# Main.net
KiCad netlist of a schematic drawn in Altium Designer
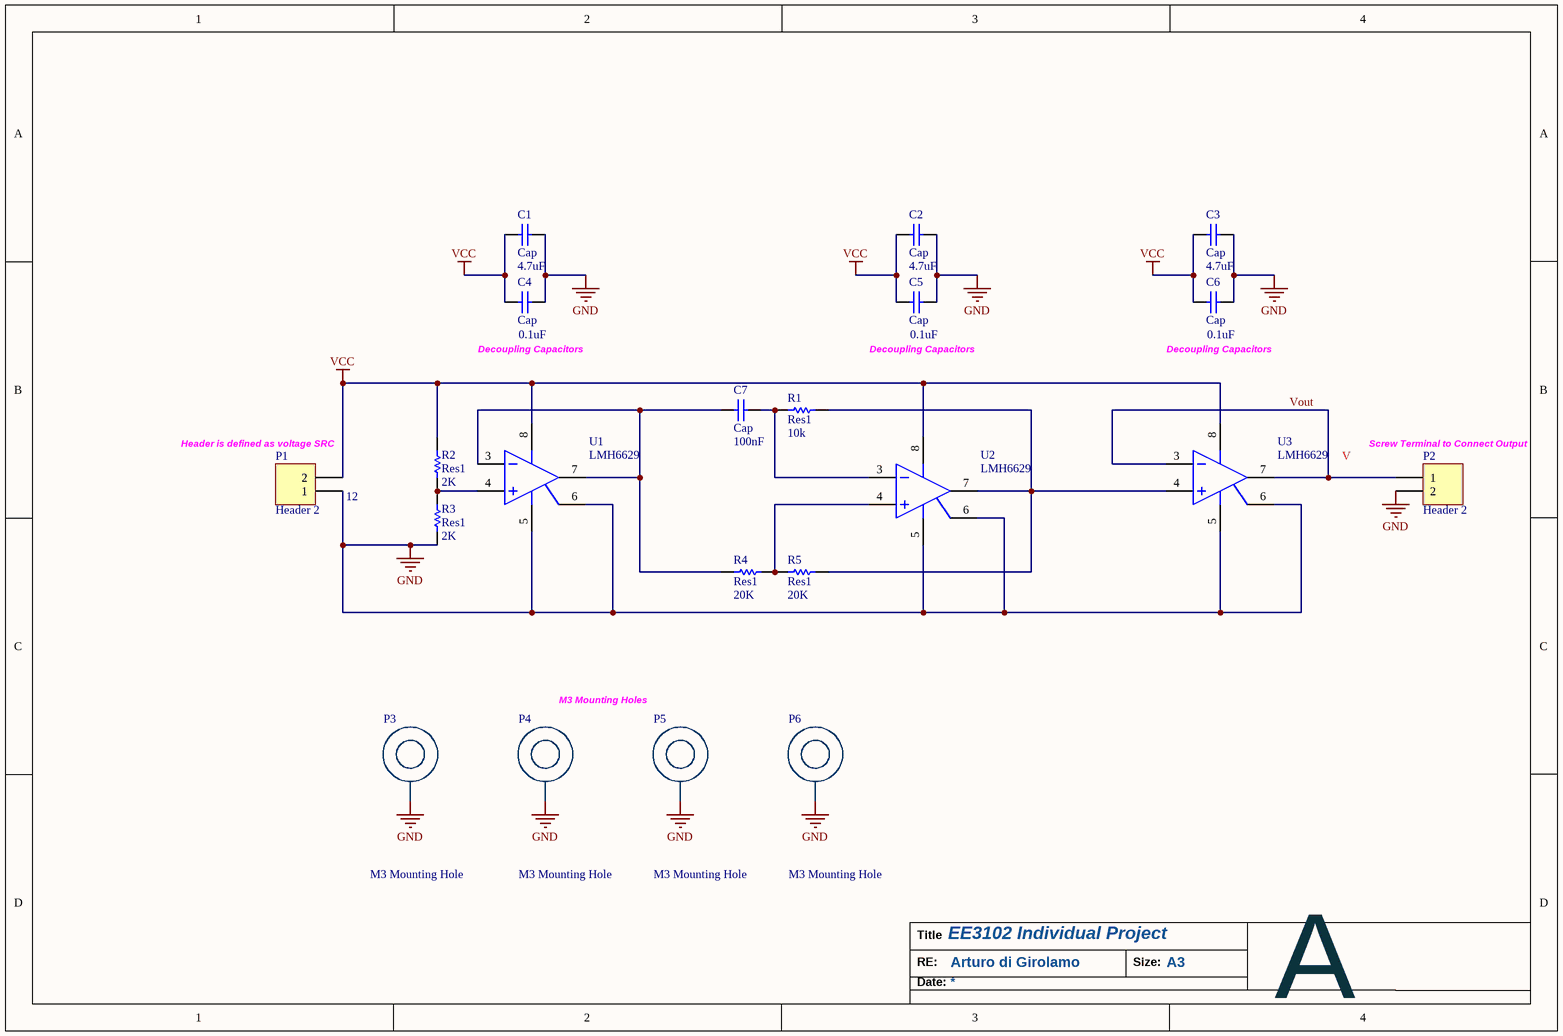
[diagram p0: Main.SchDoc]

(export (version "E")
  (design (tool "Eeschema 10.0.6"))
  (components
    (comp (ref "C1")
      (value "Cap")
      (footprint "STD_0805_C")
      (description "Capacitor")
      (fields (field (name "ALTIUM_VALUE") "4.7uF") (field (name "PUBLISHER") "Altium Limited"))
      (libsource (lib "Miscellaneous Devices") (part "Cap"))
    )
    (comp (ref "C2")
      (value "Cap")
      (footprint "STD_0805_C")
      (description "Capacitor")
      (fields (field (name "ALTIUM_VALUE") "4.7uF") (field (name "PUBLISHER") "Altium Limited"))
      (libsource (lib "Miscellaneous Devices") (part "Cap"))
    )
    (comp (ref "C3")
      (value "Cap")
      (footprint "STD_0805_C")
      (description "Capacitor")
      (fields (field (name "ALTIUM_VALUE") "4.7uF") (field (name "PUBLISHER") "Altium Limited"))
      (libsource (lib "Miscellaneous Devices") (part "Cap"))
    )
    (comp (ref "C4")
      (value "Cap")
      (footprint "STD_0805_C")
      (description "Capacitor")
      (fields (field (name "ALTIUM_VALUE") "0.1uF") (field (name "PUBLISHER") "Altium Limited"))
      (libsource (lib "Miscellaneous Devices") (part "Cap"))
    )
    (comp (ref "C5")
      (value "Cap")
      (footprint "STD_0805_C")
      (description "Capacitor")
      (fields (field (name "ALTIUM_VALUE") "0.1uF") (field (name "PUBLISHER") "Altium Limited"))
      (libsource (lib "Miscellaneous Devices") (part "Cap"))
    )
    (comp (ref "C6")
      (value "Cap")
      (footprint "STD_0805_C")
      (description "Capacitor")
      (fields (field (name "ALTIUM_VALUE") "0.1uF") (field (name "PUBLISHER") "Altium Limited"))
      (libsource (lib "Miscellaneous Devices") (part "Cap"))
    )
    (comp (ref "C7")
      (value "Cap")
      (footprint "STD_0805_C")
      (description "Capacitor")
      (fields (field (name "ALTIUM_VALUE") "100nF") (field (name "PUBLISHER") "Altium Limited"))
      (libsource (lib "Miscellaneous Devices") (part "Cap"))
    )
    (comp (ref "P1")
      (value "Header 2")
      (footprint "CUI_TB003-500-P02BE - duplicate")
      (description "Header, 2-Pin")
      (fields (field (name "ALTIUM_VALUE") "12") (field (name "PUBLISHER") "Altium Limited"))
      (libsource (lib "") (part "Header 2_1"))
    )
    (comp (ref "P2")
      (value "Header 2")
      (footprint "CUI_TB003-500-P02BE - duplicate")
      (description "Header, 2-Pin")
      (fields (field (name "PUBLISHER") "Altium Limited"))
      (libsource (lib "Miscellaneous Connectors") (part "Header 2"))
    )
    (comp (ref "P3")
      (value "M3 Mounting Hole")
      (footprint "MH-M3")
      (libsource (lib "Arturo_Approved") (part "MH-M3"))
    )
    (comp (ref "P4")
      (value "M3 Mounting Hole")
      (footprint "MH-M3")
      (libsource (lib "Arturo_Approved") (part "MH-M3"))
    )
    (comp (ref "P5")
      (value "M3 Mounting Hole")
      (footprint "MH-M3")
      (libsource (lib "Arturo_Approved") (part "MH-M3"))
    )
    (comp (ref "P6")
      (value "M3 Mounting Hole")
      (footprint "MH-M3")
      (libsource (lib "Arturo_Approved") (part "MH-M3"))
    )
    (comp (ref "R1")
      (value "Res1")
      (footprint "STD_0805_R")
      (description "Resistor")
      (fields (field (name "ALTIUM_VALUE") "10k") (field (name "PUBLISHER") "Altium Limited"))
      (libsource (lib "Miscellaneous Devices") (part "Res1"))
    )
    (comp (ref "R2")
      (value "Res1")
      (footprint "STD_0805_R")
      (description "Resistor")
      (fields (field (name "ALTIUM_VALUE") "2K") (field (name "PUBLISHER") "Altium Limited"))
      (libsource (lib "Miscellaneous Devices") (part "Res1"))
    )
    (comp (ref "R3")
      (value "Res1")
      (footprint "STD_0805_R")
      (description "Resistor")
      (fields (field (name "ALTIUM_VALUE") "2K") (field (name "PUBLISHER") "Altium Limited"))
      (libsource (lib "Miscellaneous Devices") (part "Res1"))
    )
    (comp (ref "R4")
      (value "Res1")
      (footprint "STD_0805_R")
      (description "Resistor")
      (fields (field (name "ALTIUM_VALUE") "20K") (field (name "PUBLISHER") "Altium Limited"))
      (libsource (lib "Miscellaneous Devices") (part "Res1"))
    )
    (comp (ref "R5")
      (value "Res1")
      (footprint "STD_0805_R")
      (description "Resistor")
      (fields (field (name "ALTIUM_VALUE") "20K") (field (name "PUBLISHER") "Altium Limited"))
      (libsource (lib "Miscellaneous Devices") (part "Res1"))
    )
    (comp (ref "U1")
      (value "LMH6629")
      (footprint "LMH6629")
      (libsource (lib "Arturo_Approved") (part "LMH6629"))
    )
    (comp (ref "U2")
      (value "LMH6629")
      (footprint "LMH6629")
      (libsource (lib "Arturo_Approved") (part "LMH6629"))
    )
    (comp (ref "U3")
      (value "LMH6629")
      (footprint "LMH6629")
      (libsource (lib "Arturo_Approved") (part "LMH6629"))
    )
  )
  (nets
    (net (code "1") (name "/Vout") (class "Default")
      (node (ref "P2") (pin "1") (pinfunction "1_1") (pintype "passive"))
      (node (ref "U3") (pin "3") (pinfunction "IN-_3") (pintype "passive"))
      (node (ref "U3") (pin "7") (pinfunction "OUT_7") (pintype "passive"))
    )
    (net (code "2") (name "GND") (class "Default")
      (node (ref "C1") (pin "2") (pinfunction "2_2") (pintype "passive"))
      (node (ref "C2") (pin "2") (pinfunction "2_2") (pintype "passive"))
      (node (ref "C3") (pin "2") (pinfunction "2_2") (pintype "passive"))
      (node (ref "C4") (pin "2") (pinfunction "2_2") (pintype "passive"))
      (node (ref "C5") (pin "2") (pinfunction "2_2") (pintype "passive"))
      (node (ref "C6") (pin "2") (pinfunction "2_2") (pintype "passive"))
      (node (ref "P1") (pin "1") (pinfunction "1_1") (pintype "passive"))
      (node (ref "P2") (pin "2") (pinfunction "2_2") (pintype "passive"))
      (node (ref "P3") (pin "1") (pinfunction "1_1") (pintype "passive"))
      (node (ref "P4") (pin "1") (pinfunction "1_1") (pintype "passive"))
      (node (ref "P5") (pin "1") (pinfunction "1_1") (pintype "passive"))
      (node (ref "P6") (pin "1") (pinfunction "1_1") (pintype "passive"))
      (node (ref "R3") (pin "1") (pinfunction "1_1") (pintype "passive"))
      (node (ref "U1") (pin "5") (pinfunction "V-_5") (pintype "power_in"))
      (node (ref "U1") (pin "6") (pinfunction "TAB_6") (pintype "passive"))
      (node (ref "U2") (pin "5") (pinfunction "V-_5") (pintype "power_in"))
      (node (ref "U2") (pin "6") (pinfunction "TAB_6") (pintype "passive"))
      (node (ref "U3") (pin "5") (pinfunction "V-_5") (pintype "power_in"))
      (node (ref "U3") (pin "6") (pinfunction "TAB_6") (pintype "passive"))
    )
    (net (code "3") (name "Net-(U1-IN+)") (class "Default")
      (node (ref "R2") (pin "1") (pinfunction "1_1") (pintype "passive"))
      (node (ref "R3") (pin "2") (pinfunction "2_2") (pintype "passive"))
      (node (ref "U1") (pin "4") (pinfunction "IN+_4") (pintype "passive"))
    )
    (net (code "4") (name "Net-(U1-IN-)") (class "Default")
      (node (ref "C7") (pin "1") (pinfunction "1_1") (pintype "passive"))
      (node (ref "R4") (pin "1") (pinfunction "1_1") (pintype "passive"))
      (node (ref "U1") (pin "3") (pinfunction "IN-_3") (pintype "passive"))
      (node (ref "U1") (pin "7") (pinfunction "OUT_7") (pintype "passive"))
    )
    (net (code "5") (name "Net-(U2-IN+)") (class "Default")
      (node (ref "R4") (pin "2") (pinfunction "2_2") (pintype "passive"))
      (node (ref "R5") (pin "1") (pinfunction "1_1") (pintype "passive"))
      (node (ref "U2") (pin "4") (pinfunction "IN+_4") (pintype "passive"))
    )
    (net (code "6") (name "Net-(U2-IN-)") (class "Default")
      (node (ref "C7") (pin "2") (pinfunction "2_2") (pintype "passive"))
      (node (ref "R1") (pin "1") (pinfunction "1_1") (pintype "passive"))
      (node (ref "U2") (pin "3") (pinfunction "IN-_3") (pintype "passive"))
    )
    (net (code "7") (name "Net-(U2-OUT)") (class "Default")
      (node (ref "R1") (pin "2") (pinfunction "2_2") (pintype "passive"))
      (node (ref "R5") (pin "2") (pinfunction "2_2") (pintype "passive"))
      (node (ref "U2") (pin "7") (pinfunction "OUT_7") (pintype "passive"))
      (node (ref "U3") (pin "4") (pinfunction "IN+_4") (pintype "passive"))
    )
    (net (code "8") (name "VCC") (class "Default")
      (node (ref "C1") (pin "1") (pinfunction "1_1") (pintype "passive"))
      (node (ref "C2") (pin "1") (pinfunction "1_1") (pintype "passive"))
      (node (ref "C3") (pin "1") (pinfunction "1_1") (pintype "passive"))
      (node (ref "C4") (pin "1") (pinfunction "1_1") (pintype "passive"))
      (node (ref "C5") (pin "1") (pinfunction "1_1") (pintype "passive"))
      (node (ref "C6") (pin "1") (pinfunction "1_1") (pintype "passive"))
      (node (ref "P1") (pin "2") (pinfunction "2_2") (pintype "passive"))
      (node (ref "R2") (pin "2") (pinfunction "2_2") (pintype "passive"))
      (node (ref "U1") (pin "8") (pinfunction "V+_8") (pintype "power_in"))
      (node (ref "U2") (pin "8") (pinfunction "V+_8") (pintype "power_in"))
      (node (ref "U3") (pin "8") (pinfunction "V+_8") (pintype "power_in"))
    )
  )
)
